# K60.net
KiCad netlist of a schematic drawn in Altium Designer
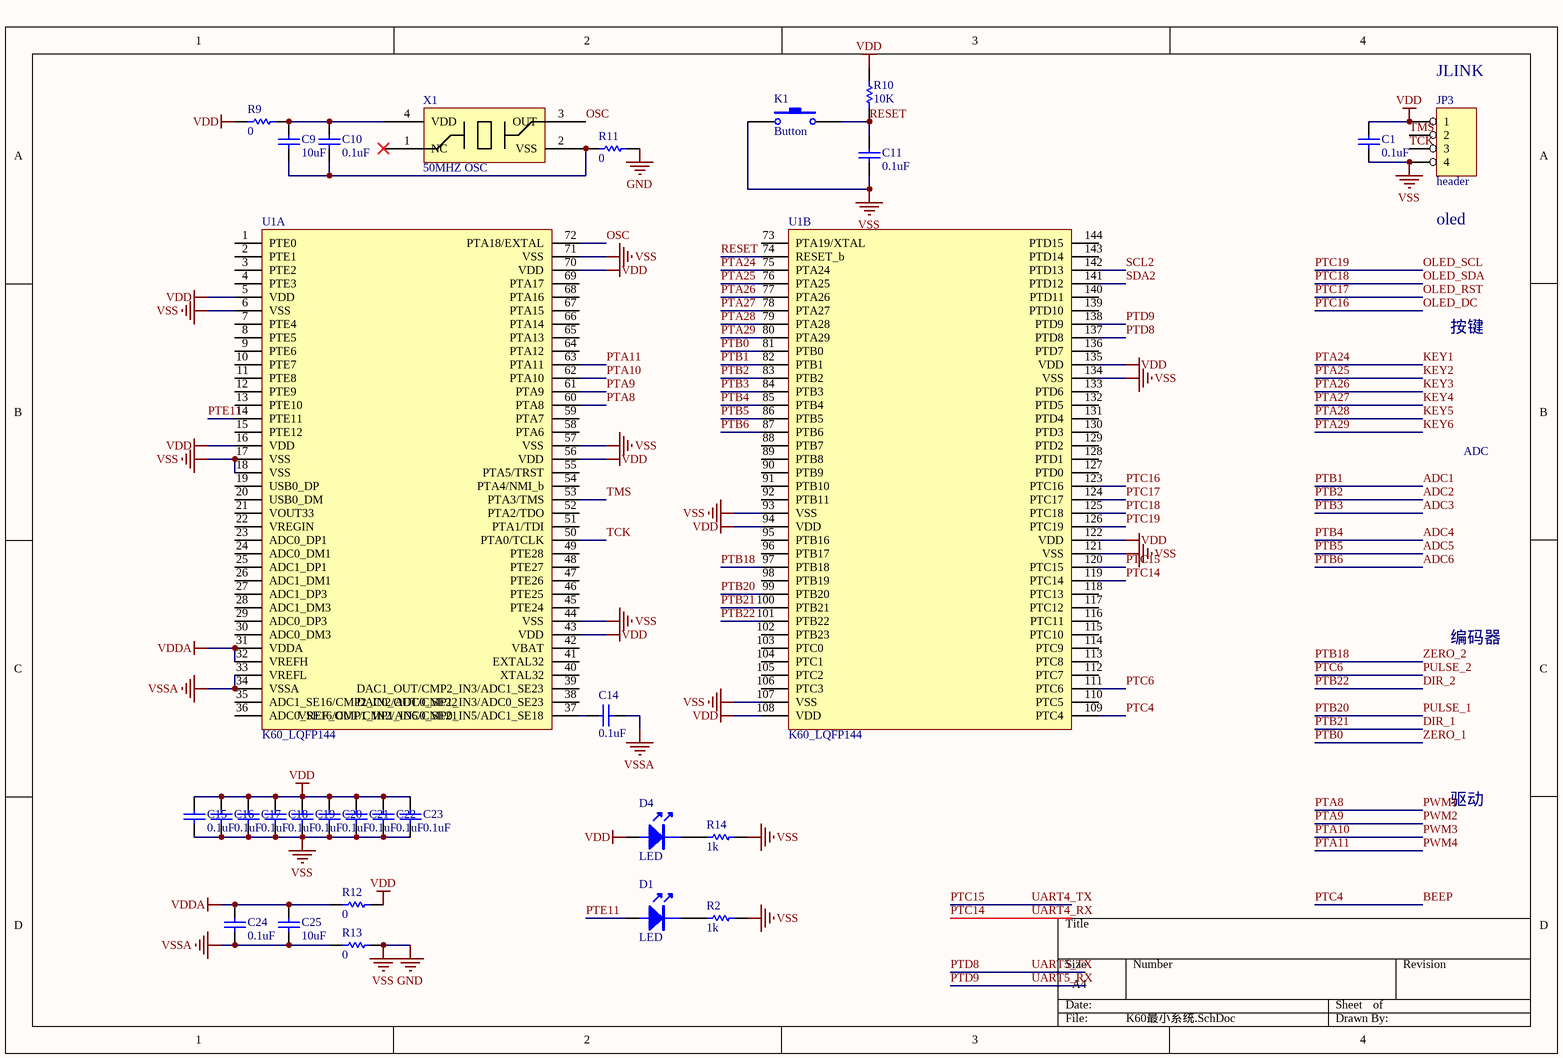
[diagram p0: K60最小系统.SchDoc]

(export (version "E")
  (design (tool "Eeschema 10.0.6"))
  (components
    (comp (ref "C1")
      (value "0.1uF")
      (footprint "0603_C")
      (description "Capacitor")
      (fields (field (name "PUBLISHER") "Altium Limited"))
      (libsource (lib "LY御用集成库") (part "CAP"))
    )
    (comp (ref "C9")
      (value "10uF")
      (footprint "0603_C")
      (description "Capacitor")
      (fields (field (name "PUBLISHER") "Altium Limited"))
      (libsource (lib "LY御用集成库") (part "CAP"))
    )
    (comp (ref "C10")
      (value "0.1uF")
      (footprint "0603_C")
      (description "Capacitor")
      (fields (field (name "PUBLISHER") "Altium Limited"))
      (libsource (lib "LY御用集成库") (part "CAP"))
    )
    (comp (ref "C11")
      (value "0.1uF")
      (footprint "0603_C")
      (description "Capacitor")
      (fields (field (name "PUBLISHER") "Altium Limited"))
      (libsource (lib "LY御用集成库") (part "CAP"))
    )
    (comp (ref "C14")
      (value "0.1uF")
      (footprint "0603_C")
      (description "Capacitor")
      (fields (field (name "PUBLISHER") "Altium Limited"))
      (libsource (lib "LY御用集成库") (part "CAP"))
    )
    (comp (ref "C15")
      (value "0.1uF")
      (footprint "0603_C")
      (description "Capacitor")
      (fields (field (name "PUBLISHER") "Altium Limited"))
      (libsource (lib "LY御用集成库") (part "CAP"))
    )
    (comp (ref "C16")
      (value "0.1uF")
      (footprint "0603_C")
      (description "Capacitor")
      (fields (field (name "PUBLISHER") "Altium Limited"))
      (libsource (lib "LY御用集成库") (part "CAP"))
    )
    (comp (ref "C17")
      (value "0.1uF")
      (footprint "0603_C")
      (description "Capacitor")
      (fields (field (name "PUBLISHER") "Altium Limited"))
      (libsource (lib "LY御用集成库") (part "CAP"))
    )
    (comp (ref "C18")
      (value "0.1uF")
      (footprint "0603_C")
      (description "Capacitor")
      (fields (field (name "PUBLISHER") "Altium Limited"))
      (libsource (lib "LY御用集成库") (part "CAP"))
    )
    (comp (ref "C19")
      (value "0.1uF")
      (footprint "0603_C")
      (description "Capacitor")
      (fields (field (name "PUBLISHER") "Altium Limited"))
      (libsource (lib "LY御用集成库") (part "CAP"))
    )
    (comp (ref "C20")
      (value "0.1uF")
      (footprint "0603_C")
      (description "Capacitor")
      (fields (field (name "PUBLISHER") "Altium Limited"))
      (libsource (lib "LY御用集成库") (part "CAP"))
    )
    (comp (ref "C21")
      (value "0.1uF")
      (footprint "0603_C")
      (description "Capacitor")
      (fields (field (name "PUBLISHER") "Altium Limited"))
      (libsource (lib "LY御用集成库") (part "CAP"))
    )
    (comp (ref "C22")
      (value "0.1uF")
      (footprint "0603_C")
      (description "Capacitor")
      (fields (field (name "PUBLISHER") "Altium Limited"))
      (libsource (lib "LY御用集成库") (part "CAP"))
    )
    (comp (ref "C23")
      (value "0.1uF")
      (footprint "0603_C")
      (description "Capacitor")
      (fields (field (name "PUBLISHER") "Altium Limited"))
      (libsource (lib "LY御用集成库") (part "CAP"))
    )
    (comp (ref "C24")
      (value "0.1uF")
      (footprint "0603_C")
      (description "Capacitor")
      (fields (field (name "PUBLISHER") "Altium Limited"))
      (libsource (lib "LY御用集成库") (part "CAP"))
    )
    (comp (ref "C25")
      (value "10uF")
      (footprint "0603_C")
      (description "Capacitor")
      (fields (field (name "PUBLISHER") "Altium Limited"))
      (libsource (lib "LY御用集成库") (part "CAP"))
    )
    (comp (ref "D1")
      (value "LED")
      (footprint "0603_LED")
      (description "LED 发光二极管")
      (libsource (lib "My Footprint") (part "LED"))
    )
    (comp (ref "D4")
      (value "LED")
      (footprint "0603_LED")
      (description "LED 发光二极管")
      (libsource (lib "My Footprint") (part "LED"))
    )
    (comp (ref "JP3") (value "header") (footprint "header4_M") (libsource (lib "LY御用集成库") (part "HEADER 4")))
    (comp (ref "K1")
      (value "Button")
      (footprint "Button_4_4*4")
      (fields (field (name "PUBLISHER") "Altium Limited"))
      (libsource (lib "LY御用集成库") (part "Button"))
    )
    (comp (ref "R2")
      (value "1k")
      (footprint "R0603")
      (description "Resistor")
      (fields (field (name "PUBLISHER") "Altium Limited"))
      (libsource (lib "LY御用集成库") (part "RES"))
    )
    (comp (ref "R9")
      (value "0")
      (footprint "R0603")
      (description "Resistor")
      (fields (field (name "PUBLISHER") "Altium Limited"))
      (libsource (lib "LY御用集成库") (part "RES"))
    )
    (comp (ref "R10")
      (value "10K")
      (footprint "R0603")
      (description "Resistor")
      (fields (field (name "PUBLISHER") "Altium Limited"))
      (libsource (lib "LY御用集成库") (part "RES"))
    )
    (comp (ref "R11")
      (value "0")
      (footprint "R0603")
      (description "Resistor")
      (fields (field (name "PUBLISHER") "Altium Limited"))
      (libsource (lib "LY御用集成库") (part "RES"))
    )
    (comp (ref "R12")
      (value "0")
      (footprint "R0603")
      (description "Resistor")
      (fields (field (name "PUBLISHER") "Altium Limited"))
      (libsource (lib "LY御用集成库") (part "RES"))
    )
    (comp (ref "R13")
      (value "0")
      (footprint "R0603")
      (description "Resistor")
      (fields (field (name "PUBLISHER") "Altium Limited"))
      (libsource (lib "LY御用集成库") (part "RES"))
    )
    (comp (ref "R14")
      (value "1k")
      (footprint "R0603")
      (description "Resistor")
      (fields (field (name "PUBLISHER") "Altium Limited"))
      (libsource (lib "LY御用集成库") (part "RES"))
    )
    (comp (ref "U1") (value "K60_LQFP144") (footprint "LQFP144") (libsource (lib "") (part "K60_LQFP144_1")))
    (comp (ref "X1") (value "50MHZ OSC") (footprint "XTAL_5032") (libsource (lib "LY御用集成库") (part "XTAL_贴片")))
  )
  (nets
    (net (code "1") (name "/ADC1") (class "Default")
      (node (ref "U1") (pin "82") (pinfunction "PTB1_82") (pintype "passive"))
    )
    (net (code "2") (name "/ADC2") (class "Default")
      (node (ref "U1") (pin "83") (pinfunction "PTB2_83") (pintype "passive"))
    )
    (net (code "3") (name "/ADC3") (class "Default")
      (node (ref "U1") (pin "84") (pinfunction "PTB3_84") (pintype "passive"))
    )
    (net (code "4") (name "/ADC4") (class "Default")
      (node (ref "U1") (pin "85") (pinfunction "PTB4_85") (pintype "passive"))
    )
    (net (code "5") (name "/ADC5") (class "Default")
      (node (ref "U1") (pin "86") (pinfunction "PTB5_86") (pintype "passive"))
    )
    (net (code "6") (name "/ADC6") (class "Default")
      (node (ref "U1") (pin "87") (pinfunction "PTB6_87") (pintype "passive"))
    )
    (net (code "7") (name "/BEEP") (class "Default")
      (node (ref "U1") (pin "109") (pinfunction "PTC4_109") (pintype "passive"))
    )
    (net (code "8") (name "/DIR_1") (class "Default")
      (node (ref "U1") (pin "100") (pinfunction "PTB21_100") (pintype "passive"))
    )
    (net (code "9") (name "/DIR_2") (class "Default")
      (node (ref "U1") (pin "101") (pinfunction "PTB22_101") (pintype "passive"))
    )
    (net (code "10") (name "/KEY1") (class "Default")
      (node (ref "U1") (pin "75") (pinfunction "PTA24_75") (pintype "passive"))
    )
    (net (code "11") (name "/KEY2") (class "Default")
      (node (ref "U1") (pin "76") (pinfunction "PTA25_76") (pintype "passive"))
    )
    (net (code "12") (name "/KEY3") (class "Default")
      (node (ref "U1") (pin "77") (pinfunction "PTA26_77") (pintype "passive"))
    )
    (net (code "13") (name "/KEY4") (class "Default")
      (node (ref "U1") (pin "78") (pinfunction "PTA27_78") (pintype "passive"))
    )
    (net (code "14") (name "/KEY5") (class "Default")
      (node (ref "U1") (pin "79") (pinfunction "PTA28_79") (pintype "passive"))
    )
    (net (code "15") (name "/KEY6") (class "Default")
      (node (ref "U1") (pin "80") (pinfunction "PTA29_80") (pintype "passive"))
    )
    (net (code "16") (name "/OLED_DC") (class "Default")
      (node (ref "U1") (pin "123") (pinfunction "PTC16_123") (pintype "passive"))
    )
    (net (code "17") (name "/OLED_RST") (class "Default")
      (node (ref "U1") (pin "124") (pinfunction "PTC17_124") (pintype "passive"))
    )
    (net (code "18") (name "/OLED_SCL") (class "Default")
      (node (ref "U1") (pin "126") (pinfunction "PTC19_126") (pintype "passive"))
    )
    (net (code "19") (name "/OLED_SDA") (class "Default")
      (node (ref "U1") (pin "125") (pinfunction "PTC18_125") (pintype "passive"))
    )
    (net (code "20") (name "/OSC") (class "Default")
      (node (ref "U1") (pin "72") (pinfunction "PTA18/EXTAL_72") (pintype "passive"))
      (node (ref "X1") (pin "3") (pinfunction "OUT_3") (pintype "passive"))
    )
    (net (code "21") (name "/PTA8") (class "Default")
      (node (ref "U1") (pin "60") (pinfunction "PTA8_60") (pintype "passive"))
    )
    (net (code "22") (name "/PTA9") (class "Default")
      (node (ref "U1") (pin "61") (pinfunction "PTA9_61") (pintype "passive"))
    )
    (net (code "23") (name "/PTA10") (class "Default")
      (node (ref "U1") (pin "62") (pinfunction "PTA10_62") (pintype "passive"))
    )
    (net (code "24") (name "/PTA11") (class "Default")
      (node (ref "U1") (pin "63") (pinfunction "PTA11_63") (pintype "passive"))
    )
    (net (code "25") (name "/PTB0") (class "Default")
      (node (ref "U1") (pin "81") (pinfunction "PTB0_81") (pintype "passive"))
    )
    (net (code "26") (name "/PTB18") (class "Default")
      (node (ref "U1") (pin "97") (pinfunction "PTB18_97") (pintype "passive"))
    )
    (net (code "27") (name "/PTB20") (class "Default")
      (node (ref "U1") (pin "99") (pinfunction "PTB20_99") (pintype "passive"))
    )
    (net (code "28") (name "/PTC6") (class "Default")
      (node (ref "U1") (pin "111") (pinfunction "PTC6_111") (pintype "passive"))
    )
    (net (code "29") (name "/PTC14") (class "Default")
      (node (ref "U1") (pin "119") (pinfunction "PTC14_119") (pintype "passive"))
    )
    (net (code "30") (name "/PTC15") (class "Default")
      (node (ref "U1") (pin "120") (pinfunction "PTC15_120") (pintype "passive"))
    )
    (net (code "31") (name "/PTD8") (class "Default")
      (node (ref "U1") (pin "137") (pinfunction "PTD8_137") (pintype "passive"))
    )
    (net (code "32") (name "/PTD9") (class "Default")
      (node (ref "U1") (pin "138") (pinfunction "PTD9_138") (pintype "passive"))
    )
    (net (code "33") (name "/PTE11") (class "Default")
      (node (ref "D1") (pin "1") (pinfunction "A_1") (pintype "passive"))
      (node (ref "U1") (pin "14") (pinfunction "PTE11_14") (pintype "passive"))
    )
    (net (code "34") (name "/RESET") (class "Default")
      (node (ref "C11") (pin "2") (pinfunction "2_2") (pintype "passive"))
      (node (ref "K1") (pin "2") (pinfunction "2_2") (pintype "passive"))
      (node (ref "R10") (pin "1") (pinfunction "1_1") (pintype "passive"))
      (node (ref "U1") (pin "74") (pinfunction "RESET_b_74") (pintype "passive"))
    )
    (net (code "35") (name "/SCL2") (class "Default")
      (node (ref "U1") (pin "142") (pinfunction "PTD13_142") (pintype "passive"))
    )
    (net (code "36") (name "/SDA2") (class "Default")
      (node (ref "U1") (pin "141") (pinfunction "PTD12_141") (pintype "passive"))
    )
    (net (code "37") (name "/TCK") (class "Default")
      (node (ref "JP3") (pin "3") (pinfunction "3_3") (pintype "passive"))
      (node (ref "U1") (pin "50") (pinfunction "PTA0/TCLK_50") (pintype "passive"))
    )
    (net (code "38") (name "/TMS") (class "Default")
      (node (ref "JP3") (pin "2") (pinfunction "2_2") (pintype "passive"))
      (node (ref "U1") (pin "53") (pinfunction "PTA3/TMS_53") (pintype "passive"))
    )
    (net (code "39") (name "GND") (class "Default")
      (node (ref "C1") (pin "1") (pinfunction "1_1") (pintype "passive"))
      (node (ref "C11") (pin "1") (pinfunction "1_1") (pintype "passive"))
      (node (ref "C15") (pin "1") (pinfunction "1_1") (pintype "passive"))
      (node (ref "C16") (pin "1") (pinfunction "1_1") (pintype "passive"))
      (node (ref "C17") (pin "1") (pinfunction "1_1") (pintype "passive"))
      (node (ref "C18") (pin "1") (pinfunction "1_1") (pintype "passive"))
      (node (ref "C19") (pin "1") (pinfunction "1_1") (pintype "passive"))
      (node (ref "C20") (pin "1") (pinfunction "1_1") (pintype "passive"))
      (node (ref "C21") (pin "1") (pinfunction "1_1") (pintype "passive"))
      (node (ref "C22") (pin "1") (pinfunction "1_1") (pintype "passive"))
      (node (ref "C23") (pin "1") (pinfunction "1_1") (pintype "passive"))
      (node (ref "JP3") (pin "4") (pinfunction "4_4") (pintype "passive"))
      (node (ref "K1") (pin "1") (pinfunction "1_1") (pintype "passive"))
      (node (ref "R11") (pin "1") (pinfunction "1_1") (pintype "passive"))
      (node (ref "R13") (pin "1") (pinfunction "1_1") (pintype "passive"))
      (node (ref "R14") (pin "1") (pinfunction "1_1") (pintype "passive"))
      (node (ref "R2") (pin "1") (pinfunction "1_1") (pintype "passive"))
      (node (ref "U1") (pin "107") (pinfunction "VSS_107") (pintype "passive"))
      (node (ref "U1") (pin "121") (pinfunction "VSS_121") (pintype "passive"))
      (node (ref "U1") (pin "134") (pinfunction "VSS_134") (pintype "passive"))
      (node (ref "U1") (pin "17") (pinfunction "VSS_17") (pintype "passive"))
      (node (ref "U1") (pin "18") (pinfunction "VSS_18") (pintype "passive"))
      (node (ref "U1") (pin "44") (pinfunction "VSS_44") (pintype "passive"))
      (node (ref "U1") (pin "57") (pinfunction "VSS_57") (pintype "passive"))
      (node (ref "U1") (pin "6") (pinfunction "VSS_6") (pintype "passive"))
      (node (ref "U1") (pin "71") (pinfunction "VSS_71") (pintype "passive"))
      (node (ref "U1") (pin "93") (pinfunction "VSS_93") (pintype "passive"))
    )
    (net (code "40") (name "Net-(D1-K)") (class "Default")
      (node (ref "D1") (pin "2") (pinfunction "K_2") (pintype "passive"))
      (node (ref "R2") (pin "2") (pinfunction "2_2") (pintype "passive"))
    )
    (net (code "41") (name "Net-(D4-K)") (class "Default")
      (node (ref "D4") (pin "2") (pinfunction "K_2") (pintype "passive"))
      (node (ref "R14") (pin "2") (pinfunction "2_2") (pintype "passive"))
    )
    (net (code "42") (name "Net-(U1A-VREF_OUT{slash}CMP1_IN5{slash}CMP0_IN5{slash}ADC1_SE18)") (class "Default")
      (node (ref "C14") (pin "2") (pinfunction "2_2") (pintype "passive"))
      (node (ref "U1") (pin "37") (pinfunction "VREF_OUT/CMP1_IN5/CMP0_IN5/ADC1_SE18_37") (pintype "passive"))
    )
    (net (code "43") (name "Net-(X1-VDD)") (class "Default")
      (node (ref "C10") (pin "2") (pinfunction "2_2") (pintype "passive"))
      (node (ref "C9") (pin "2") (pinfunction "2_2") (pintype "passive"))
      (node (ref "R9") (pin "1") (pinfunction "1_1") (pintype "passive"))
      (node (ref "X1") (pin "4") (pinfunction "VDD_4") (pintype "passive"))
    )
    (net (code "44") (name "Net-(X1-VSS)") (class "Default")
      (node (ref "C10") (pin "1") (pinfunction "1_1") (pintype "passive"))
      (node (ref "C9") (pin "1") (pinfunction "1_1") (pintype "passive"))
      (node (ref "R11") (pin "2") (pinfunction "2_2") (pintype "passive"))
      (node (ref "X1") (pin "2") (pinfunction "VSS_2") (pintype "passive"))
    )
    (net (code "45") (name "VDD") (class "Default")
      (node (ref "C1") (pin "2") (pinfunction "2_2") (pintype "passive"))
      (node (ref "C15") (pin "2") (pinfunction "2_2") (pintype "passive"))
      (node (ref "C16") (pin "2") (pinfunction "2_2") (pintype "passive"))
      (node (ref "C17") (pin "2") (pinfunction "2_2") (pintype "passive"))
      (node (ref "C18") (pin "2") (pinfunction "2_2") (pintype "passive"))
      (node (ref "C19") (pin "2") (pinfunction "2_2") (pintype "passive"))
      (node (ref "C20") (pin "2") (pinfunction "2_2") (pintype "passive"))
      (node (ref "C21") (pin "2") (pinfunction "2_2") (pintype "passive"))
      (node (ref "C22") (pin "2") (pinfunction "2_2") (pintype "passive"))
      (node (ref "C23") (pin "2") (pinfunction "2_2") (pintype "passive"))
      (node (ref "D4") (pin "1") (pinfunction "A_1") (pintype "passive"))
      (node (ref "JP3") (pin "1") (pinfunction "1_1") (pintype "passive"))
      (node (ref "R10") (pin "2") (pinfunction "2_2") (pintype "passive"))
      (node (ref "R12") (pin "1") (pinfunction "1_1") (pintype "passive"))
      (node (ref "R9") (pin "2") (pinfunction "2_2") (pintype "passive"))
      (node (ref "U1") (pin "108") (pinfunction "VDD_108") (pintype "passive"))
      (node (ref "U1") (pin "122") (pinfunction "VDD_122") (pintype "passive"))
      (node (ref "U1") (pin "135") (pinfunction "VDD_135") (pintype "passive"))
      (node (ref "U1") (pin "16") (pinfunction "VDD_16") (pintype "passive"))
      (node (ref "U1") (pin "43") (pinfunction "VDD_43") (pintype "passive"))
      (node (ref "U1") (pin "5") (pinfunction "VDD_5") (pintype "passive"))
      (node (ref "U1") (pin "56") (pinfunction "VDD_56") (pintype "passive"))
      (node (ref "U1") (pin "70") (pinfunction "VDD_70") (pintype "passive"))
      (node (ref "U1") (pin "94") (pinfunction "VDD_94") (pintype "passive"))
    )
    (net (code "46") (name "VDDA") (class "Default")
      (node (ref "C24") (pin "1") (pinfunction "1_1") (pintype "passive"))
      (node (ref "C25") (pin "2") (pinfunction "2_2") (pintype "passive"))
      (node (ref "R12") (pin "2") (pinfunction "2_2") (pintype "passive"))
      (node (ref "U1") (pin "31") (pinfunction "VDDA_31") (pintype "passive"))
      (node (ref "U1") (pin "32") (pinfunction "VREFH_32") (pintype "passive"))
    )
    (net (code "47") (name "VSSA") (class "Default")
      (node (ref "C14") (pin "1") (pinfunction "1_1") (pintype "passive"))
      (node (ref "C24") (pin "2") (pinfunction "2_2") (pintype "passive"))
      (node (ref "C25") (pin "1") (pinfunction "1_1") (pintype "passive"))
      (node (ref "R13") (pin "2") (pinfunction "2_2") (pintype "passive"))
      (node (ref "U1") (pin "33") (pinfunction "VREFL_33") (pintype "passive"))
      (node (ref "U1") (pin "34") (pinfunction "VSSA_34") (pintype "passive"))
    )
    (net (code "48") (name "unconnected-(U1A-ADC0_DM1-Pad24)") (class "Default")
      (node (ref "U1") (pin "24") (pinfunction "ADC0_DM1_24") (pintype "passive"))
    )
    (net (code "49") (name "unconnected-(U1A-ADC0_DM3-Pad30)") (class "Default")
      (node (ref "U1") (pin "30") (pinfunction "ADC0_DM3_30") (pintype "passive"))
    )
    (net (code "50") (name "unconnected-(U1A-ADC0_DP1-Pad23)") (class "Default")
      (node (ref "U1") (pin "23") (pinfunction "ADC0_DP1_23") (pintype "passive"))
    )
    (net (code "51") (name "unconnected-(U1A-ADC0_DP3-Pad29)") (class "Default")
      (node (ref "U1") (pin "29") (pinfunction "ADC0_DP3_29") (pintype "passive"))
    )
    (net (code "52") (name "unconnected-(U1A-ADC0_SE16{slash}CMP1_IN2{slash}ADC0_SE21-Pad36)") (class "Default")
      (node (ref "U1") (pin "36") (pinfunction "ADC0_SE16/CMP1_IN2/ADC0_SE21_36") (pintype "passive"))
    )
    (net (code "53") (name "unconnected-(U1A-ADC1_DM1-Pad26)") (class "Default")
      (node (ref "U1") (pin "26") (pinfunction "ADC1_DM1_26") (pintype "passive"))
    )
    (net (code "54") (name "unconnected-(U1A-ADC1_DM3-Pad28)") (class "Default")
      (node (ref "U1") (pin "28") (pinfunction "ADC1_DM3_28") (pintype "passive"))
    )
    (net (code "55") (name "unconnected-(U1A-ADC1_DP1-Pad25)") (class "Default")
      (node (ref "U1") (pin "25") (pinfunction "ADC1_DP1_25") (pintype "passive"))
    )
    (net (code "56") (name "unconnected-(U1A-ADC1_DP3-Pad27)") (class "Default")
      (node (ref "U1") (pin "27") (pinfunction "ADC1_DP3_27") (pintype "passive"))
    )
    (net (code "57") (name "unconnected-(U1A-ADC1_SE16{slash}CMP2_IN2{slash}ADC0_SE22-Pad35)") (class "Default")
      (node (ref "U1") (pin "35") (pinfunction "ADC1_SE16/CMP2_IN2/ADC0_SE22_35") (pintype "passive"))
    )
    (net (code "58") (name "unconnected-(U1A-DAC0_OUT{slash}CMP1_IN3{slash}ADC0_SE23-Pad38)") (class "Default")
      (node (ref "U1") (pin "38") (pinfunction "DAC0_OUT/CMP1_IN3/ADC0_SE23_38") (pintype "passive"))
    )
    (net (code "59") (name "unconnected-(U1A-DAC1_OUT{slash}CMP2_IN3{slash}ADC1_SE23-Pad39)") (class "Default")
      (node (ref "U1") (pin "39") (pinfunction "DAC1_OUT/CMP2_IN3/ADC1_SE23_39") (pintype "passive"))
    )
    (net (code "60") (name "unconnected-(U1A-EXTAL32-Pad41)") (class "Default")
      (node (ref "U1") (pin "41") (pinfunction "EXTAL32_41") (pintype "passive"))
    )
    (net (code "61") (name "unconnected-(U1A-PTA1{slash}TDI-Pad51)") (class "Default")
      (node (ref "U1") (pin "51") (pinfunction "PTA1/TDI_51") (pintype "passive"))
    )
    (net (code "62") (name "unconnected-(U1A-PTA2{slash}TDO-Pad52)") (class "Default")
      (node (ref "U1") (pin "52") (pinfunction "PTA2/TDO_52") (pintype "passive"))
    )
    (net (code "63") (name "unconnected-(U1A-PTA4{slash}NMI_b-Pad54)") (class "Default")
      (node (ref "U1") (pin "54") (pinfunction "PTA4/NMI_b_54") (pintype "passive"))
    )
    (net (code "64") (name "unconnected-(U1A-PTA5{slash}TRST-Pad55)") (class "Default")
      (node (ref "U1") (pin "55") (pinfunction "PTA5/TRST_55") (pintype "passive"))
    )
    (net (code "65") (name "unconnected-(U1A-PTA6-Pad58)") (class "Default")
      (node (ref "U1") (pin "58") (pinfunction "PTA6_58") (pintype "passive"))
    )
    (net (code "66") (name "unconnected-(U1A-PTA7-Pad59)") (class "Default")
      (node (ref "U1") (pin "59") (pinfunction "PTA7_59") (pintype "passive"))
    )
    (net (code "67") (name "unconnected-(U1A-PTA12-Pad64)") (class "Default")
      (node (ref "U1") (pin "64") (pinfunction "PTA12_64") (pintype "passive"))
    )
    (net (code "68") (name "unconnected-(U1A-PTA13-Pad65)") (class "Default")
      (node (ref "U1") (pin "65") (pinfunction "PTA13_65") (pintype "passive"))
    )
    (net (code "69") (name "unconnected-(U1A-PTA14-Pad66)") (class "Default")
      (node (ref "U1") (pin "66") (pinfunction "PTA14_66") (pintype "passive"))
    )
    (net (code "70") (name "unconnected-(U1A-PTA15-Pad67)") (class "Default")
      (node (ref "U1") (pin "67") (pinfunction "PTA15_67") (pintype "passive"))
    )
    (net (code "71") (name "unconnected-(U1A-PTA16-Pad68)") (class "Default")
      (node (ref "U1") (pin "68") (pinfunction "PTA16_68") (pintype "passive"))
    )
    (net (code "72") (name "unconnected-(U1A-PTA17-Pad69)") (class "Default")
      (node (ref "U1") (pin "69") (pinfunction "PTA17_69") (pintype "passive"))
    )
    (net (code "73") (name "unconnected-(U1A-PTE0-Pad1)") (class "Default")
      (node (ref "U1") (pin "1") (pinfunction "PTE0_1") (pintype "passive"))
    )
    (net (code "74") (name "unconnected-(U1A-PTE1-Pad2)") (class "Default")
      (node (ref "U1") (pin "2") (pinfunction "PTE1_2") (pintype "passive"))
    )
    (net (code "75") (name "unconnected-(U1A-PTE2-Pad3)") (class "Default")
      (node (ref "U1") (pin "3") (pinfunction "PTE2_3") (pintype "passive"))
    )
    (net (code "76") (name "unconnected-(U1A-PTE3-Pad4)") (class "Default")
      (node (ref "U1") (pin "4") (pinfunction "PTE3_4") (pintype "passive"))
    )
    (net (code "77") (name "unconnected-(U1A-PTE4-Pad7)") (class "Default")
      (node (ref "U1") (pin "7") (pinfunction "PTE4_7") (pintype "passive"))
    )
    (net (code "78") (name "unconnected-(U1A-PTE5-Pad8)") (class "Default")
      (node (ref "U1") (pin "8") (pinfunction "PTE5_8") (pintype "passive"))
    )
    (net (code "79") (name "unconnected-(U1A-PTE6-Pad9)") (class "Default")
      (node (ref "U1") (pin "9") (pinfunction "PTE6_9") (pintype "passive"))
    )
    (net (code "80") (name "unconnected-(U1A-PTE7-Pad10)") (class "Default")
      (node (ref "U1") (pin "10") (pinfunction "PTE7_10") (pintype "passive"))
    )
    (net (code "81") (name "unconnected-(U1A-PTE8-Pad11)") (class "Default")
      (node (ref "U1") (pin "11") (pinfunction "PTE8_11") (pintype "passive"))
    )
    (net (code "82") (name "unconnected-(U1A-PTE9-Pad12)") (class "Default")
      (node (ref "U1") (pin "12") (pinfunction "PTE9_12") (pintype "passive"))
    )
    (net (code "83") (name "unconnected-(U1A-PTE10-Pad13)") (class "Default")
      (node (ref "U1") (pin "13") (pinfunction "PTE10_13") (pintype "passive"))
    )
    (net (code "84") (name "unconnected-(U1A-PTE12-Pad15)") (class "Default")
      (node (ref "U1") (pin "15") (pinfunction "PTE12_15") (pintype "passive"))
    )
    (net (code "85") (name "unconnected-(U1A-PTE24-Pad45)") (class "Default")
      (node (ref "U1") (pin "45") (pinfunction "PTE24_45") (pintype "passive"))
    )
    (net (code "86") (name "unconnected-(U1A-PTE25-Pad46)") (class "Default")
      (node (ref "U1") (pin "46") (pinfunction "PTE25_46") (pintype "passive"))
    )
    (net (code "87") (name "unconnected-(U1A-PTE26-Pad47)") (class "Default")
      (node (ref "U1") (pin "47") (pinfunction "PTE26_47") (pintype "passive"))
    )
    (net (code "88") (name "unconnected-(U1A-PTE27-Pad48)") (class "Default")
      (node (ref "U1") (pin "48") (pinfunction "PTE27_48") (pintype "passive"))
    )
    (net (code "89") (name "unconnected-(U1A-PTE28-Pad49)") (class "Default")
      (node (ref "U1") (pin "49") (pinfunction "PTE28_49") (pintype "passive"))
    )
    (net (code "90") (name "unconnected-(U1A-USB0_DM-Pad20)") (class "Default")
      (node (ref "U1") (pin "20") (pinfunction "USB0_DM_20") (pintype "passive"))
    )
    (net (code "91") (name "unconnected-(U1A-USB0_DP-Pad19)") (class "Default")
      (node (ref "U1") (pin "19") (pinfunction "USB0_DP_19") (pintype "passive"))
    )
    (net (code "92") (name "unconnected-(U1A-VBAT-Pad42)") (class "Default")
      (node (ref "U1") (pin "42") (pinfunction "VBAT_42") (pintype "passive"))
    )
    (net (code "93") (name "unconnected-(U1A-VOUT33-Pad21)") (class "Default")
      (node (ref "U1") (pin "21") (pinfunction "VOUT33_21") (pintype "passive"))
    )
    (net (code "94") (name "unconnected-(U1A-VREGIN-Pad22)") (class "Default")
      (node (ref "U1") (pin "22") (pinfunction "VREGIN_22") (pintype "passive"))
    )
    (net (code "95") (name "unconnected-(U1A-XTAL32-Pad40)") (class "Default")
      (node (ref "U1") (pin "40") (pinfunction "XTAL32_40") (pintype "passive"))
    )
    (net (code "96") (name "unconnected-(U1B-PTA19{slash}XTAL-Pad73)") (class "Default")
      (node (ref "U1") (pin "73") (pinfunction "PTA19/XTAL_73") (pintype "passive"))
    )
    (net (code "97") (name "unconnected-(U1B-PTB7-Pad88)") (class "Default")
      (node (ref "U1") (pin "88") (pinfunction "PTB7_88") (pintype "passive"))
    )
    (net (code "98") (name "unconnected-(U1B-PTB8-Pad89)") (class "Default")
      (node (ref "U1") (pin "89") (pinfunction "PTB8_89") (pintype "passive"))
    )
    (net (code "99") (name "unconnected-(U1B-PTB9-Pad90)") (class "Default")
      (node (ref "U1") (pin "90") (pinfunction "PTB9_90") (pintype "passive"))
    )
    (net (code "100") (name "unconnected-(U1B-PTB10-Pad91)") (class "Default")
      (node (ref "U1") (pin "91") (pinfunction "PTB10_91") (pintype "passive"))
    )
    (net (code "101") (name "unconnected-(U1B-PTB11-Pad92)") (class "Default")
      (node (ref "U1") (pin "92") (pinfunction "PTB11_92") (pintype "passive"))
    )
    (net (code "102") (name "unconnected-(U1B-PTB16-Pad95)") (class "Default")
      (node (ref "U1") (pin "95") (pinfunction "PTB16_95") (pintype "passive"))
    )
    (net (code "103") (name "unconnected-(U1B-PTB17-Pad96)") (class "Default")
      (node (ref "U1") (pin "96") (pinfunction "PTB17_96") (pintype "passive"))
    )
    (net (code "104") (name "unconnected-(U1B-PTB19-Pad98)") (class "Default")
      (node (ref "U1") (pin "98") (pinfunction "PTB19_98") (pintype "passive"))
    )
    (net (code "105") (name "unconnected-(U1B-PTB23-Pad102)") (class "Default")
      (node (ref "U1") (pin "102") (pinfunction "PTB23_102") (pintype "passive"))
    )
    (net (code "106") (name "unconnected-(U1B-PTC0-Pad103)") (class "Default")
      (node (ref "U1") (pin "103") (pinfunction "PTC0_103") (pintype "passive"))
    )
    (net (code "107") (name "unconnected-(U1B-PTC1-Pad104)") (class "Default")
      (node (ref "U1") (pin "104") (pinfunction "PTC1_104") (pintype "passive"))
    )
    (net (code "108") (name "unconnected-(U1B-PTC2-Pad105)") (class "Default")
      (node (ref "U1") (pin "105") (pinfunction "PTC2_105") (pintype "passive"))
    )
    (net (code "109") (name "unconnected-(U1B-PTC3-Pad106)") (class "Default")
      (node (ref "U1") (pin "106") (pinfunction "PTC3_106") (pintype "passive"))
    )
    (net (code "110") (name "unconnected-(U1B-PTC5-Pad110)") (class "Default")
      (node (ref "U1") (pin "110") (pinfunction "PTC5_110") (pintype "passive"))
    )
    (net (code "111") (name "unconnected-(U1B-PTC7-Pad112)") (class "Default")
      (node (ref "U1") (pin "112") (pinfunction "PTC7_112") (pintype "passive"))
    )
    (net (code "112") (name "unconnected-(U1B-PTC8-Pad113)") (class "Default")
      (node (ref "U1") (pin "113") (pinfunction "PTC8_113") (pintype "passive"))
    )
    (net (code "113") (name "unconnected-(U1B-PTC9-Pad114)") (class "Default")
      (node (ref "U1") (pin "114") (pinfunction "PTC9_114") (pintype "passive"))
    )
    (net (code "114") (name "unconnected-(U1B-PTC10-Pad115)") (class "Default")
      (node (ref "U1") (pin "115") (pinfunction "PTC10_115") (pintype "passive"))
    )
    (net (code "115") (name "unconnected-(U1B-PTC11-Pad116)") (class "Default")
      (node (ref "U1") (pin "116") (pinfunction "PTC11_116") (pintype "passive"))
    )
    (net (code "116") (name "unconnected-(U1B-PTC12-Pad117)") (class "Default")
      (node (ref "U1") (pin "117") (pinfunction "PTC12_117") (pintype "passive"))
    )
    (net (code "117") (name "unconnected-(U1B-PTC13-Pad118)") (class "Default")
      (node (ref "U1") (pin "118") (pinfunction "PTC13_118") (pintype "passive"))
    )
    (net (code "118") (name "unconnected-(U1B-PTD0-Pad127)") (class "Default")
      (node (ref "U1") (pin "127") (pinfunction "PTD0_127") (pintype "passive"))
    )
    (net (code "119") (name "unconnected-(U1B-PTD1-Pad128)") (class "Default")
      (node (ref "U1") (pin "128") (pinfunction "PTD1_128") (pintype "passive"))
    )
    (net (code "120") (name "unconnected-(U1B-PTD2-Pad129)") (class "Default")
      (node (ref "U1") (pin "129") (pinfunction "PTD2_129") (pintype "passive"))
    )
    (net (code "121") (name "unconnected-(U1B-PTD3-Pad130)") (class "Default")
      (node (ref "U1") (pin "130") (pinfunction "PTD3_130") (pintype "passive"))
    )
    (net (code "122") (name "unconnected-(U1B-PTD4-Pad131)") (class "Default")
      (node (ref "U1") (pin "131") (pinfunction "PTD4_131") (pintype "passive"))
    )
    (net (code "123") (name "unconnected-(U1B-PTD5-Pad132)") (class "Default")
      (node (ref "U1") (pin "132") (pinfunction "PTD5_132") (pintype "passive"))
    )
    (net (code "124") (name "unconnected-(U1B-PTD6-Pad133)") (class "Default")
      (node (ref "U1") (pin "133") (pinfunction "PTD6_133") (pintype "passive"))
    )
    (net (code "125") (name "unconnected-(U1B-PTD7-Pad136)") (class "Default")
      (node (ref "U1") (pin "136") (pinfunction "PTD7_136") (pintype "passive"))
    )
    (net (code "126") (name "unconnected-(U1B-PTD10-Pad139)") (class "Default")
      (node (ref "U1") (pin "139") (pinfunction "PTD10_139") (pintype "passive"))
    )
    (net (code "127") (name "unconnected-(U1B-PTD11-Pad140)") (class "Default")
      (node (ref "U1") (pin "140") (pinfunction "PTD11_140") (pintype "passive"))
    )
    (net (code "128") (name "unconnected-(U1B-PTD14-Pad143)") (class "Default")
      (node (ref "U1") (pin "143") (pinfunction "PTD14_143") (pintype "passive"))
    )
    (net (code "129") (name "unconnected-(U1B-PTD15-Pad144)") (class "Default")
      (node (ref "U1") (pin "144") (pinfunction "PTD15_144") (pintype "passive"))
    )
    (net (code "130") (name "unconnected-(X1-NC-Pad1)") (class "Default")
      (node (ref "X1") (pin "1") (pinfunction "NC_1") (pintype "passive+no_connect"))
    )
  )
)
